# 12V_Regulator.net
KiCad netlist of a schematic drawn in Altium Designer
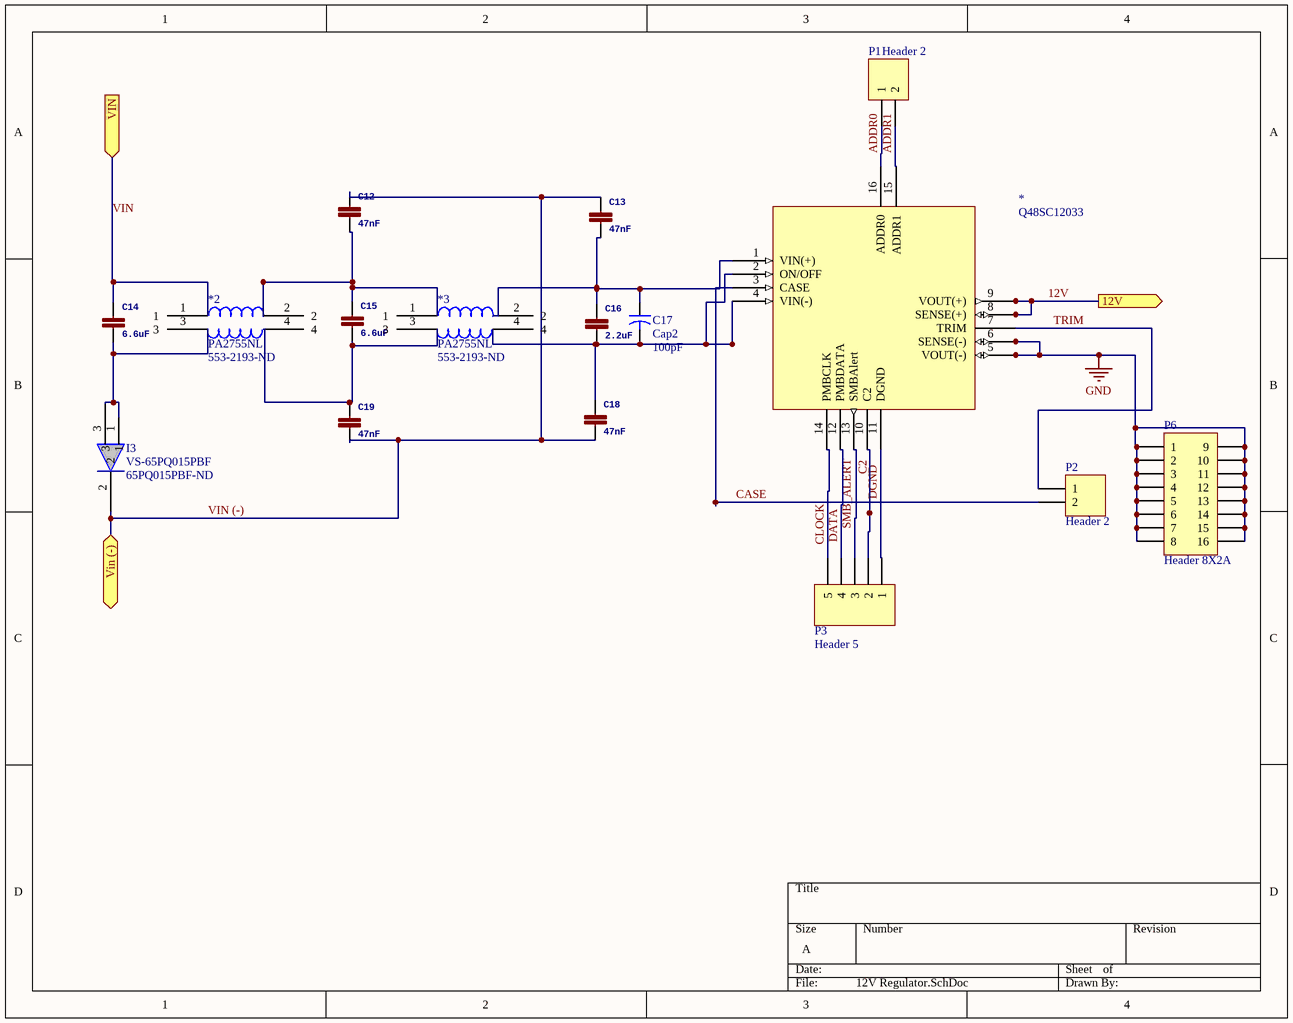
[diagram p0: 12V Regulator.SchDoc]

(export (version "E")
  (design (tool "Eeschema 10.0.6"))
  (components
    (comp (ref "*")
      (value "Q48SC12033")
      (footprint "PCBComponent_1")
      (libsource (lib "Delta_Power_supply") (part "Q48SC12033"))
    )
    (comp (ref "*2")
      (value "PA2755NL")
      (footprint "Makeni")
      (description "COMMON MODE CHOKE 14A 2LN SMD")
      (fields
        (field (name "MANUFACTURER") "Pulse Electronics Power")
        (field (name "SUPPLIER PART NUMBER 1") "553-2193-ND")
      )
      (libsource (lib "Digi_Key") (part "PA2755NL"))
    )
    (comp (ref "*3")
      (value "PA2755NL")
      (footprint "Makeni")
      (description "COMMON MODE CHOKE 14A 2LN SMD")
      (fields
        (field (name "MANUFACTURER") "Pulse Electronics Power")
        (field (name "SUPPLIER PART NUMBER 1") "553-2193-ND")
      )
      (libsource (lib "Digi_Key") (part "PA2755NL"))
    )
    (comp (ref "C12")
      (value "47nF")
      (footprint "0402-CAP")
      (libsource (lib "SparkFun-Retired") (part "2.2UF-CERCAP-07888"))
    )
    (comp (ref "C13")
      (value "47nF")
      (footprint "0402-CAP")
      (libsource (lib "SparkFun-Retired") (part "2.2UF-CERCAP-07888"))
    )
    (comp (ref "C14")
      (value "6.6uF")
      (footprint "1206")
      (libsource (lib "SparkFun-Retired") (part "2.2UF-CERCAP-10009"))
    )
    (comp (ref "C15")
      (value "6.6uF")
      (footprint "1206")
      (libsource (lib "SparkFun-Retired") (part "2.2UF-CERCAP-10009"))
    )
    (comp (ref "C16")
      (value "2.2uF")
      (footprint "0603")
      (libsource (lib "SparkFun-Capacitors") (part "1.5PF-0603-50V-16.667%"))
    )
    (comp (ref "C17")
      (value "Cap2")
      (footprint "CAPR5-4X5")
      (description "Capacitor")
      (fields (field (name "ALTIUM_VALUE") "100pF") (field (name "PUBLISHER") "Altium Limited"))
      (libsource (lib "Miscellaneous Devices") (part "Cap2"))
    )
    (comp (ref "C18")
      (value "47nF")
      (footprint "0402-CAP")
      (libsource (lib "SparkFun-Retired") (part "2.2UF-CERCAP-07888"))
    )
    (comp (ref "C19")
      (value "47nF")
      (footprint "0402-CAP")
      (libsource (lib "SparkFun-Retired") (part "2.2UF-CERCAP-07888"))
    )
    (comp (ref "I3")
      (value "VS-65PQ015PBF")
      (footprint "TO247AC")
      (description "DIODE SCHOTTKY 15V 65A TO247AC")
      (fields
        (field (name "MANUFACTURER") "Vishay Semiconductor Diodes Division")
        (field (name "SUPPLIER PART NUMBER 1") "65PQ015PBF-ND")
      )
      (libsource (lib "Digi_Key") (part "VS-65PQ015PBF"))
    )
    (comp (ref "P1")
      (value "Header 2")
      (footprint "HDR1X2")
      (description "Header, 2-Pin")
      (fields (field (name "PUBLISHER") "Altium Limited"))
      (libsource (lib "Miscellaneous Connectors") (part "Header 2"))
    )
    (comp (ref "P2")
      (value "Header 2")
      (footprint "HDR1X2")
      (description "Header, 2-Pin")
      (fields (field (name "PUBLISHER") "Altium Limited"))
      (libsource (lib "") (part "Header 2_1"))
    )
    (comp (ref "P3")
      (value "Header 5")
      (footprint "HDR1X5")
      (description "Header, 5-Pin")
      (fields (field (name "PUBLISHER") "Altium Limited"))
      (libsource (lib "Miscellaneous Connectors") (part "Header 5"))
    )
    (comp (ref "P6")
      (value "Header 8X2A")
      (footprint "HDR2X8_CEN")
      (description "Header, 8-Pin, Dual row")
      (fields (field (name "PUBLISHER") "Altium Limited"))
      (libsource (lib "Miscellaneous Connectors") (part "Header 8X2A"))
    )
  )
  (nets
    (net (code "1") (name "/12V") (class "Default")
      (node (ref "*") (pin "8") (pinfunction "SENSE(+)_8") (pintype "bidirectional"))
      (node (ref "*") (pin "9") (pinfunction "VOUT(+)_9") (pintype "output"))
    )
    (net (code "2") (name "/ADDR0") (class "Default")
      (node (ref "*") (pin "16") (pinfunction "ADDR0_16") (pintype "passive"))
      (node (ref "P1") (pin "1") (pinfunction "1_1") (pintype "passive"))
    )
    (net (code "3") (name "/ADDR1") (class "Default")
      (node (ref "*") (pin "15") (pinfunction "ADDR1_15") (pintype "passive"))
      (node (ref "P1") (pin "2") (pinfunction "2_2") (pintype "passive"))
    )
    (net (code "5") (name "/CASE") (class "Default")
      (node (ref "*") (pin "3") (pinfunction "CASE_3") (pintype "input"))
      (node (ref "P2") (pin "2") (pinfunction "2_2") (pintype "passive"))
    )
    (net (code "6") (name "/CLOCK") (class "Default")
      (node (ref "*") (pin "14") (pinfunction "PMBCLK_14") (pintype "passive"))
      (node (ref "P3") (pin "5") (pinfunction "5_5") (pintype "passive"))
    )
    (net (code "7") (name "/DATA") (class "Default")
      (node (ref "*") (pin "12") (pinfunction "PMBDATA_12") (pintype "passive"))
      (node (ref "P3") (pin "4") (pinfunction "4_4") (pintype "passive"))
    )
    (net (code "8") (name "/DGND") (class "Default")
      (node (ref "*") (pin "11") (pinfunction "DGND_11") (pintype "passive"))
      (node (ref "P3") (pin "1") (pinfunction "1_1") (pintype "passive"))
    )
    (net (code "9") (name "/SMB_ALERT") (class "Default")
      (node (ref "*") (pin "13") (pinfunction "SMBAlert_13") (pintype "output"))
      (node (ref "P3") (pin "3") (pinfunction "3_3") (pintype "passive"))
    )
    (net (code "10") (name "/TRIM") (class "Default")
      (node (ref "*") (pin "7") (pinfunction "TRIM_7") (pintype "passive"))
      (node (ref "P2") (pin "1") (pinfunction "1_1") (pintype "passive"))
    )
    (net (code "11") (name "/VIN") (class "Default")
      (node (ref "*2") (pin "1") (pinfunction "1_1") (pintype "passive"))
      (node (ref "C14") (pin "1") (pinfunction "1_1") (pintype "passive"))
    )
    (net (code "12") (name "/VIN (-)") (class "Default")
      (node (ref "C12") (pin "1") (pinfunction "1_1") (pintype "passive"))
      (node (ref "C13") (pin "1") (pinfunction "1_1") (pintype "passive"))
      (node (ref "C18") (pin "2") (pinfunction "2_2") (pintype "passive"))
      (node (ref "C19") (pin "2") (pinfunction "2_2") (pintype "passive"))
      (node (ref "I3") (pin "2") (pinfunction "2_2") (pintype "passive"))
    )
    (net (code "13") (name "GND") (class "Default")
      (node (ref "*") (pin "5") (pinfunction "VOUT(-)_5") (pintype "bidirectional"))
      (node (ref "*") (pin "6") (pinfunction "SENSE(-)_6") (pintype "bidirectional"))
      (node (ref "P6") (pin "1") (pinfunction "1_1") (pintype "passive"))
      (node (ref "P6") (pin "10") (pinfunction "10_10") (pintype "passive"))
      (node (ref "P6") (pin "11") (pinfunction "11_11") (pintype "passive"))
      (node (ref "P6") (pin "12") (pinfunction "12_12") (pintype "passive"))
      (node (ref "P6") (pin "13") (pinfunction "13_13") (pintype "passive"))
      (node (ref "P6") (pin "14") (pinfunction "14_14") (pintype "passive"))
      (node (ref "P6") (pin "15") (pinfunction "15_15") (pintype "passive"))
      (node (ref "P6") (pin "16") (pinfunction "16_16") (pintype "passive"))
      (node (ref "P6") (pin "2") (pinfunction "2_2") (pintype "passive"))
      (node (ref "P6") (pin "3") (pinfunction "3_3") (pintype "passive"))
      (node (ref "P6") (pin "4") (pinfunction "4_4") (pintype "passive"))
      (node (ref "P6") (pin "5") (pinfunction "5_5") (pintype "passive"))
      (node (ref "P6") (pin "6") (pinfunction "6_6") (pintype "passive"))
      (node (ref "P6") (pin "7") (pinfunction "7_7") (pintype "passive"))
      (node (ref "P6") (pin "8") (pinfunction "8_8") (pintype "passive"))
      (node (ref "P6") (pin "9") (pinfunction "9_9") (pintype "passive"))
    )
    (net (code "14") (name "Net-(*-C2)") (class "Default")
      (node (ref "*") (pin "10") (pinfunction "C2_10") (pintype "passive"))
      (node (ref "P3") (pin "2") (pinfunction "2_2") (pintype "passive"))
    )
    (net (code "15") (name "Net-(*-ON{slash}OFF)") (class "Default")
      (node (ref "*") (pin "2") (pinfunction "ON/OFF_2") (pintype "input"))
      (node (ref "*") (pin "4") (pinfunction "VIN(-)_4") (pintype "input"))
      (node (ref "*3") (pin "4") (pinfunction "4_4") (pintype "passive"))
      (node (ref "C16") (pin "2") (pinfunction "2_2") (pintype "passive"))
      (node (ref "C17") (pin "2") (pinfunction "2_2") (pintype "passive"))
      (node (ref "C18") (pin "1") (pinfunction "1_1") (pintype "passive"))
    )
    (net (code "16") (name "Net-(*-VIN(+))") (class "Default")
      (node (ref "*") (pin "1") (pinfunction "VIN(+)_1") (pintype "input"))
      (node (ref "*3") (pin "2") (pinfunction "2_2") (pintype "passive"))
      (node (ref "C13") (pin "2") (pinfunction "2_2") (pintype "passive"))
      (node (ref "C16") (pin "1") (pinfunction "1_1") (pintype "passive"))
      (node (ref "C17") (pin "1") (pinfunction "1_1") (pintype "passive"))
    )
    (net (code "17") (name "Net-(*2-Pad2)") (class "Default")
      (node (ref "*2") (pin "2") (pinfunction "2_2") (pintype "passive"))
      (node (ref "*3") (pin "1") (pinfunction "1_1") (pintype "passive"))
      (node (ref "C12") (pin "2") (pinfunction "2_2") (pintype "passive"))
      (node (ref "C15") (pin "1") (pinfunction "1_1") (pintype "passive"))
    )
    (net (code "18") (name "Net-(*2-Pad3)") (class "Default")
      (node (ref "*2") (pin "3") (pinfunction "3_3") (pintype "passive"))
      (node (ref "C14") (pin "2") (pinfunction "2_2") (pintype "passive"))
      (node (ref "I3") (pin "1") (pinfunction "1_1") (pintype "passive"))
      (node (ref "I3") (pin "3") (pinfunction "3_3") (pintype "passive"))
    )
    (net (code "19") (name "Net-(*2-Pad4)") (class "Default")
      (node (ref "*2") (pin "4") (pinfunction "4_4") (pintype "passive"))
      (node (ref "*3") (pin "3") (pinfunction "3_3") (pintype "passive"))
      (node (ref "C15") (pin "2") (pinfunction "2_2") (pintype "passive"))
      (node (ref "C19") (pin "1") (pinfunction "1_1") (pintype "passive"))
    )
  )
)
